# ESP32_SCH.net
KiCad netlist of a schematic drawn in Altium Designer
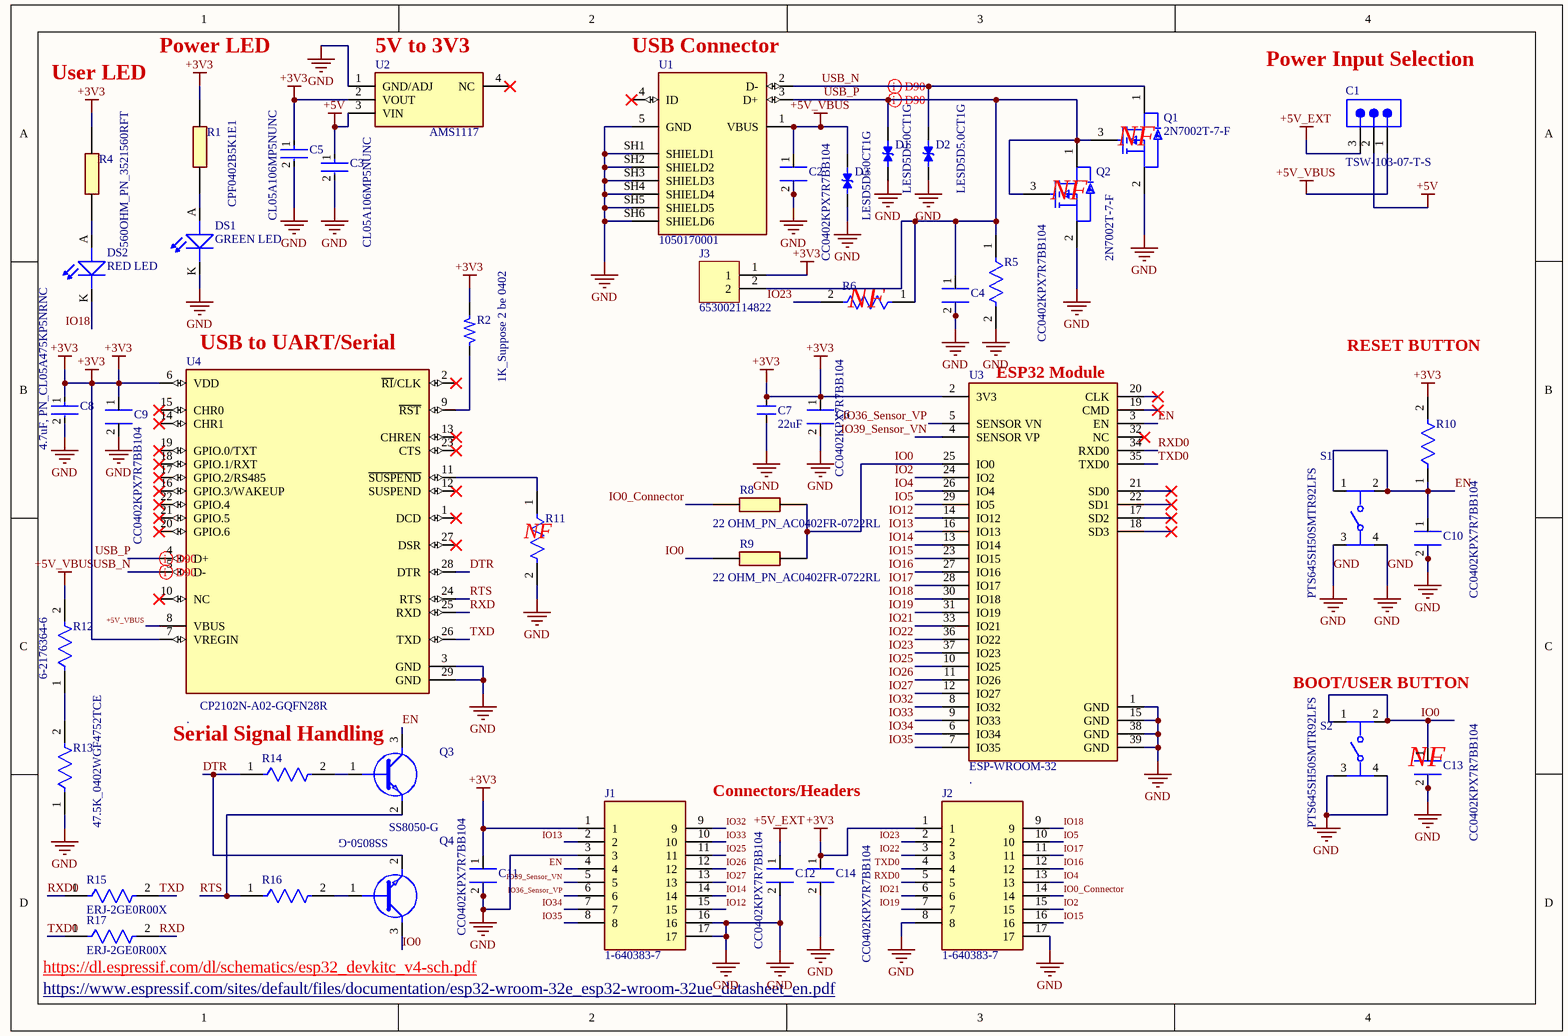
[diagram p0: ESP32_SCH.SchDoc]

(export (version "E")
  (design (tool "Eeschema 10.0.6"))
  (components
    (comp (ref "C1")
      (value "TSW-103-07-T-S")
      (footprint "x3Pins_CONN_SMTC-TSW-103-07-x-s")
      (description "0.025\" SQ Post Header, Through-hole, Vertical, -55 to 105 degC, 2.54 mm Pitch, 3-Pin, Male, RoHS")
      (libsource (lib "ESP32") (part "HDR_3x_Pins_Male_Board/Board/Cable"))
    )
    (comp (ref "C2")
      (value "CC0402KPX7R7BB104")
      (footprint "Yageo_CC0402KPX")
      (description "Multilayer Ceramic Capacitor, 0.1 uF, 10 V, ± 10%, X7R, 0402 [1005 Metric]")
      (libsource (lib "ESP32") (part "CAP_100nF_0.1uF_10V_0402"))
    )
    (comp (ref "C3")
      (value "CL05A106MP5NUNC")
      (footprint "SAMSUNG_CAP_10uF_0402")
      (description "Multilayer Ceramic Capacitor, 10 uF, 10 V, ± 20%, X5R, 0402 [1005 Metric]")
      (libsource (lib "ESP32") (part "CAP_10uF_10V_SMD_0402"))
    )
    (comp (ref "C4")
      (value "CC0402KPX7R7BB104")
      (footprint "Yageo_CC0402KPX")
      (description "Multilayer Ceramic Capacitor, 0.1 uF, 10 V, ± 10%, X7R, 0402 [1005 Metric]")
      (libsource (lib "ESP32") (part "CAP_100nF_0.1uF_10V_0402"))
    )
    (comp (ref "C5")
      (value "CL05A106MP5NUNC")
      (footprint "SAMSUNG_CAP_10uF_0402")
      (description "Multilayer Ceramic Capacitor, 10 uF, 10 V, ± 20%, X5R, 0402 [1005 Metric]")
      (libsource (lib "ESP32") (part "CAP_10uF_10V_SMD_0402"))
    )
    (comp (ref "C6")
      (value "CC0402KPX7R7BB104")
      (footprint "Yageo_CC0402KPX")
      (description "Multilayer Ceramic Capacitor, 0.1 uF, 10 V, ± 10%, X7R, 0402 [1005 Metric]")
      (libsource (lib "ESP32") (part "CAP_100nF_0.1uF_10V_0402"))
    )
    (comp (ref "C7")
      (value "22uF")
      (footprint "CAP_0805")
      (description "22µF ±20% 25V Ceramic Capacitor X5R 0805 (2012 Metric)")
      (fields
        (field (name "MANUFACTURER") "Murata")
        (field (name "MANUFACTURER PART NUMBER") "GRM21BR61E226ME44L")
      )
      (libsource (lib "ESP32") (part "CAP_22uF-25V-20%-0805"))
    )
    (comp (ref "C8")
      (value "4.7uF, PN_CL05A475KP5NRNC")
      (footprint "SAMSUNG_CAP_10uF_0402")
      (description "Multilayer Ceramic Capacitor, 10 uF, 10 V, ± 20%, X5R, 0402 [1005 Metric]")
      (libsource (lib "ESP32") (part "CAP_10uF_10V_SMD_0402"))
    )
    (comp (ref "C9")
      (value "CC0402KPX7R7BB104")
      (footprint "Yageo_CC0402KPX")
      (description "Multilayer Ceramic Capacitor, 0.1 uF, 10 V, ± 10%, X7R, 0402 [1005 Metric]")
      (libsource (lib "ESP32") (part "CAP_100nF_0.1uF_10V_0402"))
    )
    (comp (ref "C10")
      (value "CC0402KPX7R7BB104")
      (footprint "Yageo_CC0402KPX")
      (description "Multilayer Ceramic Capacitor, 0.1 uF, 10 V, ± 10%, X7R, 0402 [1005 Metric]")
      (libsource (lib "ESP32") (part "CAP_100nF_0.1uF_10V_0402"))
    )
    (comp (ref "C11")
      (value "CC0402KPX7R7BB104")
      (footprint "Yageo_CC0402KPX")
      (description "Multilayer Ceramic Capacitor, 0.1 uF, 10 V, ± 10%, X7R, 0402 [1005 Metric]")
      (libsource (lib "ESP32") (part "CAP_100nF_0.1uF_10V_0402"))
    )
    (comp (ref "C12")
      (value "CC0402KPX7R7BB104")
      (footprint "Yageo_CC0402KPX")
      (description "Multilayer Ceramic Capacitor, 0.1 uF, 10 V, ± 10%, X7R, 0402 [1005 Metric]")
      (libsource (lib "ESP32") (part "CAP_100nF_0.1uF_10V_0402"))
    )
    (comp (ref "C13")
      (value "CC0402KPX7R7BB104")
      (footprint "Yageo_CC0402KPX")
      (description "Multilayer Ceramic Capacitor, 0.1 uF, 10 V, ± 10%, X7R, 0402 [1005 Metric]")
      (libsource (lib "ESP32") (part "CAP_100nF_0.1uF_10V_0402"))
    )
    (comp (ref "C14")
      (value "CC0402KPX7R7BB104")
      (footprint "Yageo_CC0402KPX")
      (description "Multilayer Ceramic Capacitor, 0.1 uF, 10 V, ± 10%, X7R, 0402 [1005 Metric]")
      (libsource (lib "ESP32") (part "CAP_100nF_0.1uF_10V_0402"))
    )
    (comp (ref "D1")
      (value "LESD5D5.0CT1G")
      (footprint "LESD5D5.0CT1G")
      (description "Transient Voltage Suppressors for ESD Protection")
      (libsource (lib "ESP32") (part "DIO_Transient_VOl_Suppressor_ESD_PROTECTION"))
    )
    (comp (ref "D2")
      (value "LESD5D5.0CT1G")
      (footprint "LESD5D5.0CT1G")
      (description "Transient Voltage Suppressors for ESD Protection")
      (libsource (lib "ESP32") (part "DIO_Transient_VOl_Suppressor_ESD_PROTECTION"))
    )
    (comp (ref "D3")
      (value "LESD5D5.0CT1G")
      (footprint "LESD5D5.0CT1G")
      (description "Transient Voltage Suppressors for ESD Protection")
      (libsource (lib "ESP32") (part "DIO_Transient_VOl_Suppressor_ESD_PROTECTION"))
    )
    (comp (ref "DS1")
      (value "GREEN LED")
      (footprint "LED_0805")
      (description "Green 569nm LED Indication - Discrete 2.1V 0805 (2012 Metric)")
      (fields
        (field (name "MANUFACTURER") "Vishay Lite-On")
        (field (name "MANUFACTURER PART NUMBER") "LTST-C171GKT")
      )
      (libsource (lib "ESP32") (part "LED_GREEN-2.2-20mA-0805"))
    )
    (comp (ref "DS2")
      (value "RED LED")
      (footprint "LED_0805")
      (description "Red 631nm LED Indication - Discrete 2V 0805 (2012 Metric)")
      (fields
        (field (name "MANUFACTURER") "Vishay Lite-On")
        (field (name "MANUFACTURER PART NUMBER") "LTST-C171KRKT")
      )
      (libsource (lib "ESP32") (part "LED_RED-2V-20mA-0805"))
    )
    (comp (ref "J1")
      (value "1-640383-7")
      (footprint "TE_17Pin_HDR")
      (description "Conn Unshrouded Header HDR 17 POS 3.96mm Solder ST Thru-Hole Package")
      (libsource (lib "ESP32") (part "HDR_CON_x17Pin"))
    )
    (comp (ref "J2")
      (value "1-640383-7")
      (footprint "TE_17Pin_HDR")
      (description "Conn Unshrouded Header HDR 17 POS 3.96mm Solder ST Thru-Hole Package")
      (libsource (lib "ESP32") (part "HDR_CON_x17Pin"))
    )
    (comp (ref "J3")
      (value "653002114822")
      (footprint "CON2_50_653002114822_TH_ST")
      (description "2 Pins, 1 Row 1.25mm Pitch, Straight Connector, male")
      (fields (field (name "MANUFACTURER") "JST") (field (name "MATING PART NUMBER") "653002113322"))
      (libsource (lib "ESP32") (part "CON-PLG_2X1-50-ST-TH"))
    )
    (comp (ref "Q1")
      (value "2N7002T-7-F")
      (footprint "2N7002T-7-F")
      (description "Transistor MOSFET N-CH 60V 0.115A 3-Pin SOT-523 T/R - Tape and Reel")
      (libsource (lib "ESP32") (part "TRN_MOSFET_N-CH_60V_0.115A"))
    )
    (comp (ref "Q2")
      (value "2N7002T-7-F")
      (footprint "2N7002T-7-F")
      (description "Transistor MOSFET N-CH 60V 0.115A 3-Pin SOT-523 T/R - Tape and Reel")
      (libsource (lib "ESP32") (part "TRN_MOSFET_N-CH_60V_0.115A"))
    )
    (comp (ref "Q3")
      (value "SS8050-G")
      (footprint "BJT_NPN_SS8050-G")
      (description "Bipolar Transistors - BJT NPN TRANSISTOR 1.5A 40V")
      (libsource (lib "ESP32") (part "BJT_SS8050-G_NPN"))
    )
    (comp (ref "Q4")
      (value "SS8050-G")
      (footprint "BJT_NPN_SS8050-G")
      (description "Bipolar Transistors - BJT NPN TRANSISTOR 1.5A 40V")
      (libsource (lib "ESP32") (part "BJT_SS8050-G_NPN"))
    )
    (comp (ref "R1")
      (value "CPF0402B5K1E1")
      (footprint "TE_Connectivity_5.1K_0402")
      (description "Res Thin Film 0402 5.1K Ohm 0.1% 1/16W ±25ppm/°C Molded SMD SMD Paper T/R")
      (libsource (lib "ESP32") (part "RES_5.1K_0402"))
    )
    (comp (ref "R2")
      (value "1K_Suppose 2 be 0402")
      (footprint "RES_0603")
      (description "1 kOhms ±1% 0.1W, 1/10W Chip Resistor 0603 (1608 Metric) Automotive AEC-Q200 Thick Film")
      (fields (field (name "MANUFACTURER") "Walsin") (field (name "MANUFACTURER PART NUMBER") "WR06X1001FTL"))
      (libsource (lib "ESP32") (part "RES_1K-0.1W-1%-0603"))
    )
    (comp (ref "R4")
      (value "560OHM_PN_3521560RFT")
      (footprint "TE_Connectivity_5.1K_0402")
      (description "Res Thin Film 0402 5.1K Ohm 0.1% 1/16W ±25ppm/°C Molded SMD SMD Paper T/R")
      (libsource (lib "") (part "RES_5.1K_0402_2"))
    )
    (comp (ref "R5")
      (value "CRGCQ0402J10K")
      (footprint "TE_Connectivity_10K_0402")
      (description "SMD Chip Resistor, 10 kOhm, ± 5%, 63 mW, 0402 [1005 Metric], Thick Film, General Purpose")
      (libsource (lib "ESP32") (part "RES_10K_0402_SMD"))
    )
    (comp (ref "R6")
      (value "CRGCQ0402J10K")
      (footprint "TE_Connectivity_10K_0402")
      (description "SMD Chip Resistor, 10 kOhm, ± 5%, 63 mW, 0402 [1005 Metric], Thick Film, General Purpose")
      (libsource (lib "ESP32") (part "RES_10K_0402_SMD"))
    )
    (comp (ref "R8")
      (value "22 OHM_PN_AC0402FR-0722RL")
      (footprint "TE_Connectivity_5.1K_0402")
      (description "Res Thin Film 0402 5.1K Ohm 0.1% 1/16W ±25ppm/°C Molded SMD SMD Paper T/R")
      (libsource (lib "") (part "RES_5.1K_0402_1"))
    )
    (comp (ref "R9")
      (value "22 OHM_PN_AC0402FR-0722RL")
      (footprint "TE_Connectivity_5.1K_0402")
      (description "Res Thin Film 0402 5.1K Ohm 0.1% 1/16W ±25ppm/°C Molded SMD SMD Paper T/R")
      (libsource (lib "") (part "RES_5.1K_0402_1"))
    )
    (comp (ref "R10")
      (value "CRGCQ0402J10K")
      (footprint "TE_Connectivity_10K_0402")
      (description "SMD Chip Resistor, 10 kOhm, ± 5%, 63 mW, 0402 [1005 Metric], Thick Film, General Purpose")
      (libsource (lib "ESP32") (part "RES_10K_0402_SMD"))
    )
    (comp (ref "R11")
      (value "NF")
      (footprint "TE_Connectivity_10K_0402")
      (description "SMD Chip Resistor, 10 kOhm, ± 5%, 63 mW, 0402 [1005 Metric], Thick Film, General Purpose")
      (libsource (lib "ESP32") (part "RES_10K_0402_SMD"))
    )
    (comp (ref "R12")
      (value "6-2176364-6")
      (footprint "TE_Connectivity_22.1K_0402")
      (description "Res Precision Thin Film 22.1kOhm 0.1% 62.5mW 10ppm/°C 2-Pin 0402 SMD T/R")
      (libsource (lib "NOUMANPCBLIB") (part "RES_22.1KOHM_0402"))
    )
    (comp (ref "R13")
      (value "47.5K_0402WGF4752TCE")
      (footprint "TE_Connectivity_22.1K_0402")
      (description "Res Precision Thin Film 22.1kOhm 0.1% 62.5mW 10ppm/°C 2-Pin 0402 SMD T/R")
      (libsource (lib "NOUMANPCBLIB") (part "RES_22.1KOHM_0402"))
    )
    (comp (ref "R14")
      (value "CRGCQ0402J10K")
      (footprint "TE_Connectivity_10K_0402")
      (description "SMD Chip Resistor, 10 kOhm, ± 5%, 63 mW, 0402 [1005 Metric], Thick Film, General Purpose")
      (libsource (lib "ESP32") (part "RES_10K_0402_SMD"))
    )
    (comp (ref "R15")
      (value "ERJ-2GE0R00X")
      (footprint "PANASONIC_0_OHM_0402")
      (description "SMD Chip Resistor, Jumper, 0 ohm, 100 mW, 0402 [1005 Metric], Thick Film, General Purpose")
      (libsource (lib "ESP32") (part "RES_0_OHM_0402"))
    )
    (comp (ref "R16")
      (value "CRGCQ0402J10K")
      (footprint "TE_Connectivity_10K_0402")
      (description "SMD Chip Resistor, 10 kOhm, ± 5%, 63 mW, 0402 [1005 Metric], Thick Film, General Purpose")
      (libsource (lib "ESP32") (part "RES_10K_0402_SMD"))
    )
    (comp (ref "R17")
      (value "ERJ-2GE0R00X")
      (footprint "PANASONIC_0_OHM_0402")
      (description "SMD Chip Resistor, Jumper, 0 ohm, 100 mW, 0402 [1005 Metric], Thick Film, General Purpose")
      (libsource (lib "ESP32") (part "RES_0_OHM_0402"))
    )
    (comp (ref "S1")
      (value "PTS645SH50SMTR92LFS")
      (footprint "C&K Tactile SW")
      (description "Switch Tactile N.O. SPST Round Button Gull Wing 0.05A 12VDC 100000Cycles 1.96N SMD T/R")
      (libsource (lib "ESP32") (part "SW_Tactile_0.05A,12VDC_SMD"))
    )
    (comp (ref "S2")
      (value "PTS645SH50SMTR92LFS")
      (footprint "C&K Tactile SW")
      (description "Switch Tactile N.O. SPST Round Button Gull Wing 0.05A 12VDC 100000Cycles 1.96N SMD T/R")
      (libsource (lib "ESP32") (part "SW_Tactile_0.05A,12VDC_SMD"))
    )
    (comp (ref "U1")
      (value "1050170001")
      (footprint "MOLEX_1050170001")
      (description "USB - micro B USB 2.0 Receptacle Connector 5 Position Surface Mount, Right Angle; Through Hole")
      (libsource (lib "ESP32") (part "USB_Micro_B 2.0_MOLEX"))
    )
    (comp (ref "U2")
      (value "AMS1117")
      (footprint "ASM1117-3V3_SOT229P700X180-4N")
      (description "ASM1117, 5V to 3V3, 1A.")
      (libsource (lib "ESP32") (part "VREG_1117_1A_LDO"))
    )
    (comp (ref "U3")
      (value ".")
      (footprint "ESP-WROOM-32")
      (description "IC SPRESSIF ESP32 BLUETOOTH WIFI MESP-WROOM-32 is a powerful, generic Wi-Fi+BT+BLE MCU module")
      (libsource (lib "ESP32") (part "IC_Espressif_ESP-WROOM-32_eec"))
    )
    (comp (ref "U4")
      (value ".")
      (footprint "CP21002N-A02")
      (description "Integrated Circuit Interface USB for UART Controller; 3-3.6V; -40+85 deg.C; SMD; QFN28")
      (libsource (lib "ESP32") (part "IC_CP2102N-A02-GQFN28R"))
    )
  )
  (nets
    (net (code "1") (name "+3V3") (class "Default")
      (node (ref "C11") (pin "1") (pinfunction "1_1") (pintype "passive"))
      (node (ref "C14") (pin "1") (pinfunction "1_1") (pintype "passive"))
      (node (ref "C5") (pin "1") (pinfunction "1_1") (pintype "passive"))
      (node (ref "C6") (pin "1") (pinfunction "1_1") (pintype "passive"))
      (node (ref "C7") (pin "2") (pinfunction "2_2") (pintype "passive"))
      (node (ref "C8") (pin "1") (pinfunction "1_1") (pintype "passive"))
      (node (ref "C9") (pin "1") (pinfunction "1_1") (pintype "passive"))
      (node (ref "J1") (pin "1") (pinfunction "1_1") (pintype "passive"))
      (node (ref "J2") (pin "1") (pinfunction "1_1") (pintype "passive"))
      (node (ref "J3") (pin "1") (pinfunction "1_1") (pintype "passive"))
      (node (ref "R1") (pin "1") (pinfunction "1_1") (pintype "passive"))
      (node (ref "R10") (pin "2") (pinfunction "2_2") (pintype "passive"))
      (node (ref "R2") (pin "2") (pinfunction "2_2") (pintype "passive"))
      (node (ref "R4") (pin "2") (pinfunction "2_2") (pintype "passive"))
      (node (ref "U2") (pin "2") (pinfunction "VOUT_2") (pintype "passive"))
      (node (ref "U3") (pin "2") (pinfunction "3V3_2") (pintype "passive"))
      (node (ref "U4") (pin "6") (pinfunction "VDD_6") (pintype "bidirectional"))
      (node (ref "U4") (pin "7") (pinfunction "VREGIN_7") (pintype "bidirectional"))
    )
    (net (code "2") (name "+5V") (class "Default")
      (node (ref "C1") (pin "2") (pinfunction "2_2") (pintype "passive"))
      (node (ref "C3") (pin "1") (pinfunction "1_1") (pintype "passive"))
      (node (ref "U2") (pin "3") (pinfunction "VIN_3") (pintype "passive"))
    )
    (net (code "3") (name "+5V_EXT") (class "Default")
      (node (ref "C1") (pin "3") (pinfunction "3_3") (pintype "passive"))
      (node (ref "C12") (pin "1") (pinfunction "1_1") (pintype "passive"))
    )
    (net (code "4") (name "+5V_VBUS") (class "Default")
      (node (ref "C1") (pin "1") (pinfunction "1_1") (pintype "passive"))
      (node (ref "C2") (pin "1") (pinfunction "1_1") (pintype "passive"))
      (node (ref "D3") (pin "2") (pinfunction "2_2") (pintype "passive"))
      (node (ref "R12") (pin "2") (pinfunction "2_2") (pintype "passive"))
      (node (ref "U1") (pin "1") (pinfunction "VBUS_1") (pintype "power_in"))
      (node (ref "U4") (pin "8") (pinfunction "VBUS_8") (pintype "passive"))
    )
    (net (code "5") (name "/DTR") (class "Default")
      (node (ref "Q4") (pin "2") (pinfunction "E_2") (pintype "passive"))
      (node (ref "R14") (pin "1") (pinfunction "1_1") (pintype "passive"))
      (node (ref "U4") (pin "28") (pinfunction "DTR_28") (pintype "bidirectional"))
    )
    (net (code "6") (name "/EN") (class "Default")
      (node (ref "C10") (pin "1") (pinfunction "1_1") (pintype "passive"))
      (node (ref "J1") (pin "4") (pinfunction "4_4") (pintype "passive"))
      (node (ref "Q3") (pin "3") (pinfunction "C_3") (pintype "passive"))
      (node (ref "R10") (pin "1") (pinfunction "1_1") (pintype "passive"))
      (node (ref "S1") (pin "1") (pinfunction "1_1") (pintype "passive"))
      (node (ref "S1") (pin "2") (pinfunction "2_2") (pintype "passive"))
      (node (ref "U3") (pin "3") (pinfunction "EN_3") (pintype "passive"))
    )
    (net (code "7") (name "/IO0") (class "Default")
      (node (ref "C13") (pin "1") (pinfunction "1_1") (pintype "passive"))
      (node (ref "Q4") (pin "3") (pinfunction "C_3") (pintype "passive"))
      (node (ref "R8") (pin "2") (pinfunction "2_2") (pintype "passive"))
      (node (ref "R9") (pin "1") (pinfunction "1_1") (pintype "passive"))
      (node (ref "R9") (pin "2") (pinfunction "2_2") (pintype "passive"))
      (node (ref "S2") (pin "1") (pinfunction "1_1") (pintype "passive"))
      (node (ref "S2") (pin "2") (pinfunction "2_2") (pintype "passive"))
      (node (ref "U3") (pin "25") (pinfunction "IO0_25") (pintype "passive"))
    )
    (net (code "8") (name "/IO0_Connector") (class "Default")
      (node (ref "J2") (pin "14") (pinfunction "14_14") (pintype "passive"))
      (node (ref "R8") (pin "1") (pinfunction "1_1") (pintype "passive"))
    )
    (net (code "9") (name "/IO2") (class "Default")
      (node (ref "J2") (pin "15") (pinfunction "15_15") (pintype "passive"))
      (node (ref "U3") (pin "24") (pinfunction "IO2_24") (pintype "passive"))
    )
    (net (code "10") (name "/IO4") (class "Default")
      (node (ref "J2") (pin "13") (pinfunction "13_13") (pintype "passive"))
      (node (ref "U3") (pin "26") (pinfunction "IO4_26") (pintype "passive"))
    )
    (net (code "11") (name "/IO5") (class "Default")
      (node (ref "J2") (pin "10") (pinfunction "10_10") (pintype "passive"))
      (node (ref "U3") (pin "29") (pinfunction "IO5_29") (pintype "passive"))
    )
    (net (code "12") (name "/IO12") (class "Default")
      (node (ref "J1") (pin "15") (pinfunction "15_15") (pintype "passive"))
      (node (ref "U3") (pin "14") (pinfunction "IO12_14") (pintype "passive"))
    )
    (net (code "13") (name "/IO13") (class "Default")
      (node (ref "J1") (pin "2") (pinfunction "2_2") (pintype "passive"))
      (node (ref "U3") (pin "16") (pinfunction "IO13_16") (pintype "passive"))
    )
    (net (code "14") (name "/IO14") (class "Default")
      (node (ref "J1") (pin "14") (pinfunction "14_14") (pintype "passive"))
      (node (ref "U3") (pin "13") (pinfunction "IO14_13") (pintype "passive"))
    )
    (net (code "15") (name "/IO15") (class "Default")
      (node (ref "J2") (pin "16") (pinfunction "16_16") (pintype "passive"))
      (node (ref "U3") (pin "23") (pinfunction "IO15_23") (pintype "passive"))
    )
    (net (code "16") (name "/IO16") (class "Default")
      (node (ref "J2") (pin "12") (pinfunction "12_12") (pintype "passive"))
      (node (ref "U3") (pin "27") (pinfunction "IO16_27") (pintype "passive"))
    )
    (net (code "17") (name "/IO17") (class "Default")
      (node (ref "J2") (pin "11") (pinfunction "11_11") (pintype "passive"))
      (node (ref "U3") (pin "28") (pinfunction "IO17_28") (pintype "passive"))
    )
    (net (code "18") (name "/IO18") (class "Default")
      (node (ref "DS2") (pin "K") (pinfunction "CATHODE_K") (pintype "passive"))
      (node (ref "J2") (pin "9") (pinfunction "9_9") (pintype "passive"))
      (node (ref "U3") (pin "30") (pinfunction "IO18_30") (pintype "passive"))
    )
    (net (code "19") (name "/IO19") (class "Default")
      (node (ref "J2") (pin "7") (pinfunction "7_7") (pintype "passive"))
      (node (ref "U3") (pin "31") (pinfunction "IO19_31") (pintype "passive"))
    )
    (net (code "20") (name "/IO21") (class "Default")
      (node (ref "J2") (pin "6") (pinfunction "6_6") (pintype "passive"))
      (node (ref "U3") (pin "33") (pinfunction "IO21_33") (pintype "passive"))
    )
    (net (code "21") (name "/IO22") (class "Default")
      (node (ref "J2") (pin "3") (pinfunction "3_3") (pintype "passive"))
      (node (ref "U3") (pin "36") (pinfunction "IO22_36") (pintype "passive"))
    )
    (net (code "22") (name "/IO23") (class "Default")
      (node (ref "J2") (pin "2") (pinfunction "2_2") (pintype "passive"))
      (node (ref "R6") (pin "2") (pinfunction "2_2") (pintype "passive"))
      (node (ref "U3") (pin "37") (pinfunction "IO23_37") (pintype "passive"))
    )
    (net (code "23") (name "/IO25") (class "Default")
      (node (ref "J1") (pin "11") (pinfunction "11_11") (pintype "passive"))
      (node (ref "U3") (pin "10") (pinfunction "IO25_10") (pintype "passive"))
    )
    (net (code "24") (name "/IO26") (class "Default")
      (node (ref "J1") (pin "12") (pinfunction "12_12") (pintype "passive"))
      (node (ref "U3") (pin "11") (pinfunction "IO26_11") (pintype "passive"))
    )
    (net (code "25") (name "/IO27") (class "Default")
      (node (ref "J1") (pin "13") (pinfunction "13_13") (pintype "passive"))
      (node (ref "U3") (pin "12") (pinfunction "IO27_12") (pintype "passive"))
    )
    (net (code "26") (name "/IO32") (class "Default")
      (node (ref "J1") (pin "9") (pinfunction "9_9") (pintype "passive"))
      (node (ref "U3") (pin "8") (pinfunction "IO32_8") (pintype "passive"))
    )
    (net (code "27") (name "/IO33") (class "Default")
      (node (ref "J1") (pin "10") (pinfunction "10_10") (pintype "passive"))
      (node (ref "U3") (pin "9") (pinfunction "IO33_9") (pintype "passive"))
    )
    (net (code "28") (name "/IO34") (class "Default")
      (node (ref "J1") (pin "7") (pinfunction "7_7") (pintype "passive"))
      (node (ref "U3") (pin "6") (pinfunction "IO34_6") (pintype "passive"))
    )
    (net (code "29") (name "/IO35") (class "Default")
      (node (ref "J1") (pin "8") (pinfunction "8_8") (pintype "passive"))
      (node (ref "U3") (pin "7") (pinfunction "IO35_7") (pintype "passive"))
    )
    (net (code "30") (name "/IO36_Sensor_VP") (class "Default")
      (node (ref "J1") (pin "6") (pinfunction "6_6") (pintype "passive"))
      (node (ref "U3") (pin "5") (pinfunction "SENSOR_VN_5") (pintype "passive"))
    )
    (net (code "31") (name "/IO39_Sensor_VN") (class "Default")
      (node (ref "J1") (pin "5") (pinfunction "5_5") (pintype "passive"))
      (node (ref "U3") (pin "4") (pinfunction "SENSOR_VP_4") (pintype "passive"))
    )
    (net (code "32") (name "/RTS") (class "Default")
      (node (ref "Q3") (pin "2") (pinfunction "E_2") (pintype "passive"))
      (node (ref "R16") (pin "1") (pinfunction "1_1") (pintype "passive"))
      (node (ref "U4") (pin "24") (pinfunction "RTS_24") (pintype "bidirectional"))
    )
    (net (code "33") (name "/RXD") (class "Default")
      (node (ref "R17") (pin "2") (pinfunction "2_2") (pintype "passive"))
      (node (ref "U4") (pin "25") (pinfunction "RXD_25") (pintype "bidirectional"))
    )
    (net (code "34") (name "/RXD0") (class "Default")
      (node (ref "J2") (pin "5") (pinfunction "5_5") (pintype "passive"))
      (node (ref "R15") (pin "1") (pinfunction "1_1") (pintype "passive"))
      (node (ref "U3") (pin "34") (pinfunction "RXD0_34") (pintype "passive"))
    )
    (net (code "35") (name "/TXD") (class "Default")
      (node (ref "R15") (pin "2") (pinfunction "2_2") (pintype "passive"))
      (node (ref "U4") (pin "26") (pinfunction "TXD_26") (pintype "bidirectional"))
    )
    (net (code "36") (name "/TXD0") (class "Default")
      (node (ref "J2") (pin "4") (pinfunction "4_4") (pintype "passive"))
      (node (ref "R17") (pin "1") (pinfunction "1_1") (pintype "passive"))
      (node (ref "U3") (pin "35") (pinfunction "TXD0_35") (pintype "passive"))
    )
    (net (code "37") (name "/USB_N") (class "Default")
      (node (ref "D2") (pin "2") (pinfunction "2_2") (pintype "passive"))
      (node (ref "Q1") (pin "1") (pinfunction "Drain_1") (pintype "passive"))
      (node (ref "U1") (pin "2") (pinfunction "D-_2") (pintype "bidirectional"))
      (node (ref "U4") (pin "5") (pinfunction "D-_5") (pintype "bidirectional"))
    )
    (net (code "38") (name "/USB_P") (class "Default")
      (node (ref "C4") (pin "1") (pinfunction "1_1") (pintype "passive"))
      (node (ref "D1") (pin "2") (pinfunction "2_2") (pintype "passive"))
      (node (ref "J3") (pin "2") (pinfunction "2_2") (pintype "passive"))
      (node (ref "Q1") (pin "3") (pinfunction "Source_3") (pintype "passive"))
      (node (ref "Q2") (pin "1") (pinfunction "Drain_1") (pintype "passive"))
      (node (ref "Q2") (pin "3") (pinfunction "Source_3") (pintype "passive"))
      (node (ref "R5") (pin "1") (pinfunction "1_1") (pintype "passive"))
      (node (ref "R6") (pin "1") (pinfunction "1_1") (pintype "passive"))
      (node (ref "U1") (pin "3") (pinfunction "D+_3") (pintype "bidirectional"))
      (node (ref "U4") (pin "4") (pinfunction "D+_4") (pintype "bidirectional"))
    )
    (net (code "39") (name "GND") (class "Default")
      (node (ref "C10") (pin "2") (pinfunction "2_2") (pintype "passive"))
      (node (ref "C11") (pin "2") (pinfunction "2_2") (pintype "passive"))
      (node (ref "C12") (pin "2") (pinfunction "2_2") (pintype "passive"))
      (node (ref "C13") (pin "2") (pinfunction "2_2") (pintype "passive"))
      (node (ref "C14") (pin "2") (pinfunction "2_2") (pintype "passive"))
      (node (ref "C2") (pin "2") (pinfunction "2_2") (pintype "passive"))
      (node (ref "C3") (pin "2") (pinfunction "2_2") (pintype "passive"))
      (node (ref "C4") (pin "2") (pinfunction "2_2") (pintype "passive"))
      (node (ref "C5") (pin "2") (pinfunction "2_2") (pintype "passive"))
      (node (ref "C6") (pin "2") (pinfunction "2_2") (pintype "passive"))
      (node (ref "C7") (pin "1") (pinfunction "1_1") (pintype "passive"))
      (node (ref "C8") (pin "2") (pinfunction "2_2") (pintype "passive"))
      (node (ref "C9") (pin "2") (pinfunction "2_2") (pintype "passive"))
      (node (ref "D1") (pin "1") (pinfunction "1_1") (pintype "passive"))
      (node (ref "D2") (pin "1") (pinfunction "1_1") (pintype "passive"))
      (node (ref "D3") (pin "1") (pinfunction "1_1") (pintype "passive"))
      (node (ref "DS1") (pin "K") (pinfunction "CATHODE_K") (pintype "passive"))
      (node (ref "J1") (pin "16") (pinfunction "16_16") (pintype "passive"))
      (node (ref "J1") (pin "17") (pinfunction "17_17") (pintype "passive"))
      (node (ref "J1") (pin "3") (pinfunction "3_3") (pintype "passive"))
      (node (ref "J2") (pin "17") (pinfunction "17_17") (pintype "passive"))
      (node (ref "J2") (pin "8") (pinfunction "8_8") (pintype "passive"))
      (node (ref "Q1") (pin "2") (pinfunction "Gate_2") (pintype "passive"))
      (node (ref "Q2") (pin "2") (pinfunction "Gate_2") (pintype "passive"))
      (node (ref "R11") (pin "2") (pinfunction "2_2") (pintype "passive"))
      (node (ref "R13") (pin "1") (pinfunction "1_1") (pintype "passive"))
      (node (ref "R5") (pin "2") (pinfunction "2_2") (pintype "passive"))
      (node (ref "S1") (pin "3") (pinfunction "3_3") (pintype "passive"))
      (node (ref "S1") (pin "4") (pinfunction "4_4") (pintype "passive"))
      (node (ref "S2") (pin "3") (pinfunction "3_3") (pintype "passive"))
      (node (ref "S2") (pin "4") (pinfunction "4_4") (pintype "passive"))
      (node (ref "U1") (pin "5") (pinfunction "GND_5") (pintype "power_in"))
      (node (ref "U1") (pin "SH1") (pinfunction "SHIELD1_SH1") (pintype "passive"))
      (node (ref "U1") (pin "SH2") (pinfunction "SHIELD2_SH2") (pintype "passive"))
      (node (ref "U1") (pin "SH3") (pinfunction "SHIELD3_SH3") (pintype "passive"))
      (node (ref "U1") (pin "SH4") (pinfunction "SHIELD4_SH4") (pintype "passive"))
      (node (ref "U1") (pin "SH5") (pinfunction "SHIELD5_SH5") (pintype "passive"))
      (node (ref "U1") (pin "SH6") (pinfunction "SHIELD6_SH6") (pintype "passive"))
      (node (ref "U2") (pin "1") (pinfunction "GND/ADJ_1") (pintype "passive"))
      (node (ref "U3") (pin "1") (pinfunction "GND_1") (pintype "passive"))
      (node (ref "U3") (pin "15") (pinfunction "GND_15") (pintype "passive"))
      (node (ref "U3") (pin "38") (pinfunction "GND_38") (pintype "passive"))
      (node (ref "U3") (pin "39") (pinfunction "GND_39") (pintype "passive"))
      (node (ref "U4") (pin "29") (pinfunction "GND_29") (pintype "passive"))
      (node (ref "U4") (pin "3") (pinfunction "GND_3") (pintype "passive"))
    )
    (net (code "40") (name "Net-(DS1-ANODE)") (class "Default")
      (node (ref "DS1") (pin "A") (pinfunction "ANODE_A") (pintype "passive"))
      (node (ref "R1") (pin "2") (pinfunction "2_2") (pintype "passive"))
    )
    (net (code "41") (name "Net-(DS2-ANODE)") (class "Default")
      (node (ref "DS2") (pin "A") (pinfunction "ANODE_A") (pintype "passive"))
      (node (ref "R4") (pin "1") (pinfunction "1_1") (pintype "passive"))
    )
    (net (code "42") (name "Net-(Q3-B)") (class "Default")
      (node (ref "Q3") (pin "1") (pinfunction "B_1") (pintype "passive"))
      (node (ref "R14") (pin "2") (pinfunction "2_2") (pintype "passive"))
    )
    (net (code "43") (name "Net-(Q4-B)") (class "Default")
      (node (ref "Q4") (pin "1") (pinfunction "B_1") (pintype "passive"))
      (node (ref "R16") (pin "2") (pinfunction "2_2") (pintype "passive"))
    )
    (net (code "44") (name "Net-(R12-Pad1)") (class "Default")
      (node (ref "R12") (pin "1") (pinfunction "1_1") (pintype "passive"))
      (node (ref "R13") (pin "2") (pinfunction "2_2") (pintype "passive"))
    )
    (net (code "45") (name "Net-(U4-~{RST})") (class "Default")
      (node (ref "R2") (pin "1") (pinfunction "1_1") (pintype "passive"))
      (node (ref "U4") (pin "9") (pinfunction "~{RST}_9") (pintype "bidirectional"))
    )
    (net (code "46") (name "Net-(U4-~{SUSPEND})") (class "Default")
      (node (ref "R11") (pin "1") (pinfunction "1_1") (pintype "passive"))
      (node (ref "U4") (pin "11") (pinfunction "~{SUSPEND}_11") (pintype "bidirectional"))
    )
    (net (code "47") (name "unconnected-(U1-ID-Pad4)") (class "Default")
      (node (ref "U1") (pin "4") (pinfunction "ID_4") (pintype "bidirectional+no_connect"))
    )
    (net (code "48") (name "unconnected-(U2-NC-Pad4)") (class "Default")
      (node (ref "U2") (pin "4") (pinfunction "NC_4") (pintype "passive+no_connect"))
    )
    (net (code "49") (name "unconnected-(U3-CLK-Pad20)") (class "Default")
      (node (ref "U3") (pin "20") (pinfunction "CLK_20") (pintype "passive+no_connect"))
    )
    (net (code "50") (name "unconnected-(U3-CMD-Pad19)") (class "Default")
      (node (ref "U3") (pin "19") (pinfunction "CMD_19") (pintype "passive+no_connect"))
    )
    (net (code "51") (name "unconnected-(U3-NC-Pad32)") (class "Default")
      (node (ref "U3") (pin "32") (pinfunction "NC_32") (pintype "passive+no_connect"))
    )
    (net (code "52") (name "unconnected-(U3-SD0-Pad21)") (class "Default")
      (node (ref "U3") (pin "21") (pinfunction "SD0_21") (pintype "passive+no_connect"))
    )
    (net (code "53") (name "unconnected-(U3-SD1-Pad22)") (class "Default")
      (node (ref "U3") (pin "22") (pinfunction "SD1_22") (pintype "passive+no_connect"))
    )
    (net (code "54") (name "unconnected-(U3-SD2-Pad17)") (class "Default")
      (node (ref "U3") (pin "17") (pinfunction "SD2_17") (pintype "passive+no_connect"))
    )
    (net (code "55") (name "unconnected-(U3-SD3-Pad18)") (class "Default")
      (node (ref "U3") (pin "18") (pinfunction "SD3_18") (pintype "passive+no_connect"))
    )
    (net (code "56") (name "unconnected-(U4-CHR0-Pad15)") (class "Default")
      (node (ref "U4") (pin "15") (pinfunction "CHR0_15") (pintype "bidirectional+no_connect"))
    )
    (net (code "57") (name "unconnected-(U4-CHR1-Pad14)") (class "Default")
      (node (ref "U4") (pin "14") (pinfunction "CHR1_14") (pintype "bidirectional+no_connect"))
    )
    (net (code "58") (name "unconnected-(U4-CHREN-Pad13)") (class "Default")
      (node (ref "U4") (pin "13") (pinfunction "CHREN_13") (pintype "bidirectional+no_connect"))
    )
    (net (code "59") (name "unconnected-(U4-CTS-Pad23)") (class "Default")
      (node (ref "U4") (pin "23") (pinfunction "CTS_23") (pintype "bidirectional+no_connect"))
    )
    (net (code "60") (name "unconnected-(U4-DCD-Pad1)") (class "Default")
      (node (ref "U4") (pin "1") (pinfunction "DCD_1") (pintype "bidirectional+no_connect"))
    )
    (net (code "61") (name "unconnected-(U4-DSR-Pad27)") (class "Default")
      (node (ref "U4") (pin "27") (pinfunction "DSR_27") (pintype "bidirectional+no_connect"))
    )
    (net (code "62") (name "unconnected-(U4-GPIO.0{slash}TXT-Pad19)") (class "Default")
      (node (ref "U4") (pin "19") (pinfunction "GPIO.0/TXT_19") (pintype "bidirectional+no_connect"))
    )
    (net (code "63") (name "unconnected-(U4-GPIO.1{slash}RXT-Pad18)") (class "Default")
      (node (ref "U4") (pin "18") (pinfunction "GPIO.1/RXT_18") (pintype "bidirectional+no_connect"))
    )
    (net (code "64") (name "unconnected-(U4-GPIO.2{slash}RS485-Pad17)") (class "Default")
      (node (ref "U4") (pin "17") (pinfunction "GPIO.2/RS485_17") (pintype "bidirectional+no_connect"))
    )
    (net (code "65") (name "unconnected-(U4-GPIO.3{slash}WAKEUP-Pad16)") (class "Default")
      (node (ref "U4") (pin "16") (pinfunction "GPIO.3/WAKEUP_16") (pintype "bidirectional+no_connect"))
    )
    (net (code "66") (name "unconnected-(U4-GPIO.4-Pad22)") (class "Default")
      (node (ref "U4") (pin "22") (pinfunction "GPIO.4_22") (pintype "bidirectional+no_connect"))
    )
    (net (code "67") (name "unconnected-(U4-GPIO.5-Pad21)") (class "Default")
      (node (ref "U4") (pin "21") (pinfunction "GPIO.5_21") (pintype "bidirectional+no_connect"))
    )
    (net (code "68") (name "unconnected-(U4-GPIO.6-Pad20)") (class "Default")
      (node (ref "U4") (pin "20") (pinfunction "GPIO.6_20") (pintype "bidirectional+no_connect"))
    )
    (net (code "69") (name "unconnected-(U4-NC-Pad10)") (class "Default")
      (node (ref "U4") (pin "10") (pinfunction "NC_10") (pintype "bidirectional+no_connect"))
    )
    (net (code "70") (name "unconnected-(U4-SUSPEND-Pad12)") (class "Default")
      (node (ref "U4") (pin "12") (pinfunction "SUSPEND_12") (pintype "bidirectional+no_connect"))
    )
    (net (code "71") (name "unconnected-(U4-~{RI}{slash}CLK-Pad2)") (class "Default")
      (node (ref "U4") (pin "2") (pinfunction "~{RI}/CLK_2") (pintype "bidirectional+no_connect"))
    )
  )
)
